# P02_MCU.net
KiCad netlist of a schematic drawn in Altium Designer
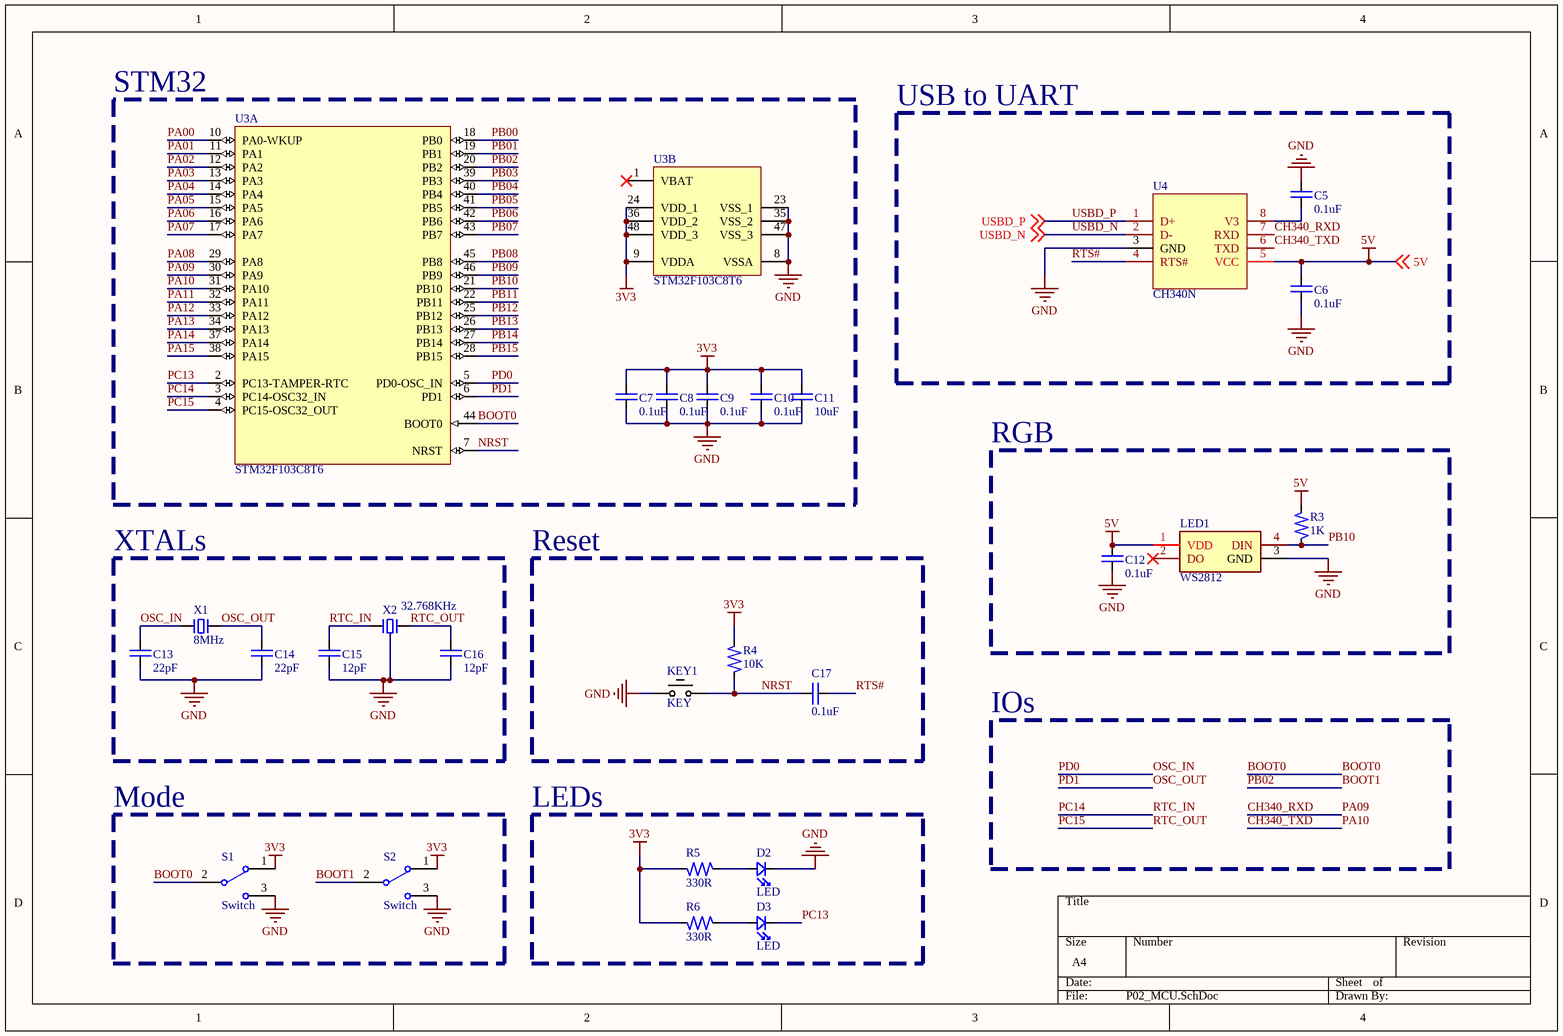
[diagram p0: P02_MCU.SchDoc]

(export (version "E")
  (design (tool "Eeschema 10.0.6"))
  (components
    (comp (ref "C5")
      (value "0.1uF")
      (footprint "C_0603")
      (description "无极性电容")
      (libsource (lib "Schlib") (part "C"))
    )
    (comp (ref "C6")
      (value "0.1uF")
      (footprint "C_0603")
      (description "无极性电容")
      (libsource (lib "Schlib") (part "C"))
    )
    (comp (ref "C7")
      (value "0.1uF")
      (footprint "C_0603")
      (description "无极性电容")
      (libsource (lib "Schlib") (part "C"))
    )
    (comp (ref "C8")
      (value "0.1uF")
      (footprint "C_0603")
      (description "无极性电容")
      (libsource (lib "Schlib") (part "C"))
    )
    (comp (ref "C9")
      (value "0.1uF")
      (footprint "C_0603")
      (description "无极性电容")
      (libsource (lib "Schlib") (part "C"))
    )
    (comp (ref "C10")
      (value "0.1uF")
      (footprint "C_0603")
      (description "无极性电容")
      (libsource (lib "Schlib") (part "C"))
    )
    (comp (ref "C11")
      (value "10uF")
      (footprint "C_0603")
      (description "无极性电容")
      (libsource (lib "Schlib") (part "C"))
    )
    (comp (ref "C12")
      (value "0.1uF")
      (footprint "C_0603")
      (description "无极性电容")
      (libsource (lib "Schlib") (part "C"))
    )
    (comp (ref "C13")
      (value "22pF")
      (footprint "C_0603")
      (description "无极性电容")
      (libsource (lib "Schlib") (part "C"))
    )
    (comp (ref "C14")
      (value "22pF")
      (footprint "C_0603")
      (description "无极性电容")
      (libsource (lib "Schlib") (part "C"))
    )
    (comp (ref "C15")
      (value "12pF")
      (footprint "C_0603")
      (description "无极性电容")
      (libsource (lib "Schlib") (part "C"))
    )
    (comp (ref "C16")
      (value "12pF")
      (footprint "C_0603")
      (description "无极性电容")
      (libsource (lib "Schlib") (part "C"))
    )
    (comp (ref "C17")
      (value "0.1uF")
      (footprint "C_0603")
      (description "无极性电容")
      (libsource (lib "Schlib") (part "C"))
    )
    (comp (ref "D2")
      (value "LED")
      (footprint "LED_0603")
      (description "Diode")
      (libsource (lib "Schlib") (part "LED"))
    )
    (comp (ref "D3")
      (value "LED")
      (footprint "LED_0603")
      (description "Diode")
      (libsource (lib "Schlib") (part "LED"))
    )
    (comp (ref "KEY1")
      (value "KEY")
      (footprint "KEY")
      (description "通用2脚按键")
      (libsource (lib "Schlib") (part "KEY"))
    )
    (comp (ref "LED1") (value "WS2812") (footprint "SMD5050") (libsource (lib "Schlib") (part "WS2812")))
    (comp (ref "R3")
      (value "1K")
      (footprint "R_0603")
      (description "Resistor")
      (libsource (lib "Schlib") (part "R"))
    )
    (comp (ref "R4")
      (value "10K")
      (footprint "R_0603")
      (description "Resistor")
      (libsource (lib "Schlib") (part "R"))
    )
    (comp (ref "R5")
      (value "330R")
      (footprint "R_0603")
      (description "Resistor")
      (libsource (lib "Schlib") (part "R"))
    )
    (comp (ref "R6")
      (value "330R")
      (footprint "R_0603")
      (description "Resistor")
      (libsource (lib "Schlib") (part "R"))
    )
    (comp (ref "S1")
      (value "Switch")
      (footprint "Sliding Switch_3P")
      (libsource (lib "Schlib") (part "Switch"))
    )
    (comp (ref "S2")
      (value "Switch")
      (footprint "Sliding Switch_3P")
      (libsource (lib "Schlib") (part "Switch"))
    )
    (comp (ref "U3")
      (value "STM32F103C8T6")
      (footprint "QFP-48")
      (libsource (lib "Schlib") (part "STM32F103C8T6"))
    )
    (comp (ref "U4")
      (value "CH340N")
      (footprint "SOP-8")
      (description "USB转UART")
      (libsource (lib "Schlib") (part "CH340N"))
    )
    (comp (ref "X1")
      (value "8MHz")
      (footprint "XTAL_HC49S")
      (description "晶振")
      (libsource (lib "Schlib") (part "XTAL"))
    )
    (comp (ref "X2")
      (value "32.768KHz")
      (footprint "XTAL_DT26")
      (description "晶振")
      (libsource (lib "Schlib") (part "XTAL_RTC"))
    )
  )
  (nets
    (net (code "1") (name "/BOOT0") (class "Default")
      (node (ref "S1") (pin "2") (pinfunction "2_2") (pintype "passive"))
      (node (ref "U3") (pin "44") (pinfunction "BOOT0_44") (pintype "input"))
    )
    (net (code "2") (name "/BOOT1") (class "Default")
      (node (ref "S2") (pin "2") (pinfunction "2_2") (pintype "passive"))
      (node (ref "U3") (pin "20") (pinfunction "PB2_20") (pintype "bidirectional"))
    )
    (net (code "3") (name "/CH340_RXD") (class "Default")
      (node (ref "U3") (pin "30") (pinfunction "PA9_30") (pintype "bidirectional"))
      (node (ref "U4") (pin "7") (pinfunction "RXD_7") (pintype "passive"))
    )
    (net (code "4") (name "/CH340_TXD") (class "Default")
      (node (ref "U3") (pin "31") (pinfunction "PA10_31") (pintype "bidirectional"))
      (node (ref "U4") (pin "6") (pinfunction "TXD_6") (pintype "passive"))
    )
    (net (code "5") (name "/NRST") (class "Default")
      (node (ref "C17") (pin "1") (pinfunction "1_1") (pintype "passive"))
      (node (ref "KEY1") (pin "1") (pinfunction "1_1") (pintype "passive"))
      (node (ref "R4") (pin "2") (pinfunction "2_2") (pintype "passive"))
      (node (ref "U3") (pin "7") (pinfunction "NRST_7") (pintype "bidirectional"))
    )
    (net (code "6") (name "/OSC_IN") (class "Default")
      (node (ref "C13") (pin "1") (pinfunction "1_1") (pintype "passive"))
      (node (ref "U3") (pin "5") (pinfunction "PD0-OSC_IN_5") (pintype "bidirectional"))
      (node (ref "X1") (pin "1") (pinfunction "1_1") (pintype "passive"))
    )
    (net (code "7") (name "/OSC_OUT") (class "Default")
      (node (ref "C14") (pin "1") (pinfunction "1_1") (pintype "passive"))
      (node (ref "U3") (pin "6") (pinfunction "PD1_6") (pintype "bidirectional"))
      (node (ref "X1") (pin "2") (pinfunction "2_2") (pintype "passive"))
    )
    (net (code "8") (name "/PA00") (class "Default")
      (node (ref "U3") (pin "10") (pinfunction "PA0-WKUP_10") (pintype "bidirectional"))
    )
    (net (code "9") (name "/PA01") (class "Default")
      (node (ref "U3") (pin "11") (pinfunction "PA1_11") (pintype "bidirectional"))
    )
    (net (code "10") (name "/PA02") (class "Default")
      (node (ref "U3") (pin "12") (pinfunction "PA2_12") (pintype "bidirectional"))
    )
    (net (code "11") (name "/PA03") (class "Default")
      (node (ref "U3") (pin "13") (pinfunction "PA3_13") (pintype "bidirectional"))
    )
    (net (code "12") (name "/PA04") (class "Default")
      (node (ref "U3") (pin "14") (pinfunction "PA4_14") (pintype "bidirectional"))
    )
    (net (code "13") (name "/PA05") (class "Default")
      (node (ref "U3") (pin "15") (pinfunction "PA5_15") (pintype "bidirectional"))
    )
    (net (code "14") (name "/PA06") (class "Default")
      (node (ref "U3") (pin "16") (pinfunction "PA6_16") (pintype "bidirectional"))
    )
    (net (code "15") (name "/PA07") (class "Default")
      (node (ref "U3") (pin "17") (pinfunction "PA7_17") (pintype "bidirectional"))
    )
    (net (code "16") (name "/PA08") (class "Default")
      (node (ref "U3") (pin "29") (pinfunction "PA8_29") (pintype "bidirectional"))
    )
    (net (code "17") (name "/PA11") (class "Default")
      (node (ref "U3") (pin "32") (pinfunction "PA11_32") (pintype "bidirectional"))
    )
    (net (code "18") (name "/PA12") (class "Default")
      (node (ref "U3") (pin "33") (pinfunction "PA12_33") (pintype "bidirectional"))
    )
    (net (code "19") (name "/PA13") (class "Default")
      (node (ref "U3") (pin "34") (pinfunction "PA13_34") (pintype "bidirectional"))
    )
    (net (code "20") (name "/PA14") (class "Default")
      (node (ref "U3") (pin "37") (pinfunction "PA14_37") (pintype "bidirectional"))
    )
    (net (code "21") (name "/PA15") (class "Default")
      (node (ref "U3") (pin "38") (pinfunction "PA15_38") (pintype "bidirectional"))
    )
    (net (code "22") (name "/PB00") (class "Default")
      (node (ref "U3") (pin "18") (pinfunction "PB0_18") (pintype "bidirectional"))
    )
    (net (code "23") (name "/PB01") (class "Default")
      (node (ref "U3") (pin "19") (pinfunction "PB1_19") (pintype "bidirectional"))
    )
    (net (code "24") (name "/PB03") (class "Default")
      (node (ref "U3") (pin "39") (pinfunction "PB3_39") (pintype "bidirectional"))
    )
    (net (code "25") (name "/PB04") (class "Default")
      (node (ref "U3") (pin "40") (pinfunction "PB4_40") (pintype "bidirectional"))
    )
    (net (code "26") (name "/PB05") (class "Default")
      (node (ref "U3") (pin "41") (pinfunction "PB5_41") (pintype "bidirectional"))
    )
    (net (code "27") (name "/PB06") (class "Default")
      (node (ref "U3") (pin "42") (pinfunction "PB6_42") (pintype "bidirectional"))
    )
    (net (code "28") (name "/PB07") (class "Default")
      (node (ref "U3") (pin "43") (pinfunction "PB7_43") (pintype "bidirectional"))
    )
    (net (code "29") (name "/PB08") (class "Default")
      (node (ref "U3") (pin "45") (pinfunction "PB8_45") (pintype "bidirectional"))
    )
    (net (code "30") (name "/PB09") (class "Default")
      (node (ref "U3") (pin "46") (pinfunction "PB9_46") (pintype "bidirectional"))
    )
    (net (code "31") (name "/PB10") (class "Default")
      (node (ref "LED1") (pin "4") (pinfunction "DIN_4") (pintype "passive"))
      (node (ref "R3") (pin "1") (pinfunction "1_1") (pintype "passive"))
      (node (ref "U3") (pin "21") (pinfunction "PB10_21") (pintype "bidirectional"))
    )
    (net (code "32") (name "/PB11") (class "Default")
      (node (ref "U3") (pin "22") (pinfunction "PB11_22") (pintype "bidirectional"))
    )
    (net (code "33") (name "/PB12") (class "Default")
      (node (ref "U3") (pin "25") (pinfunction "PB12_25") (pintype "bidirectional"))
    )
    (net (code "34") (name "/PB13") (class "Default")
      (node (ref "U3") (pin "26") (pinfunction "PB13_26") (pintype "bidirectional"))
    )
    (net (code "35") (name "/PB14") (class "Default")
      (node (ref "U3") (pin "27") (pinfunction "PB14_27") (pintype "bidirectional"))
    )
    (net (code "36") (name "/PB15") (class "Default")
      (node (ref "U3") (pin "28") (pinfunction "PB15_28") (pintype "bidirectional"))
    )
    (net (code "37") (name "/PC13") (class "Default")
      (node (ref "D3") (pin "1") (pinfunction "1_1") (pintype "passive"))
      (node (ref "U3") (pin "2") (pinfunction "PC13-TAMPER-RTC_2") (pintype "bidirectional"))
    )
    (net (code "38") (name "/PC14") (class "Default")
      (node (ref "C15") (pin "1") (pinfunction "1_1") (pintype "passive"))
      (node (ref "U3") (pin "3") (pinfunction "PC14-OSC32_IN_3") (pintype "bidirectional"))
      (node (ref "X2") (pin "1") (pinfunction "1_1") (pintype "passive"))
    )
    (net (code "39") (name "/PC15") (class "Default")
      (node (ref "C16") (pin "1") (pinfunction "1_1") (pintype "passive"))
      (node (ref "U3") (pin "4") (pinfunction "PC15-OSC32_OUT_4") (pintype "bidirectional"))
      (node (ref "X2") (pin "2") (pinfunction "2_2") (pintype "passive"))
    )
    (net (code "40") (name "/RTS#") (class "Default")
      (node (ref "C17") (pin "2") (pinfunction "2_2") (pintype "passive"))
      (node (ref "U4") (pin "4") (pinfunction "RTS#_4") (pintype "passive"))
    )
    (net (code "41") (name "3V3") (class "Default")
      (node (ref "C10") (pin "2") (pinfunction "2_2") (pintype "passive"))
      (node (ref "C11") (pin "2") (pinfunction "2_2") (pintype "passive"))
      (node (ref "C7") (pin "1") (pinfunction "1_1") (pintype "passive"))
      (node (ref "C8") (pin "2") (pinfunction "2_2") (pintype "passive"))
      (node (ref "C9") (pin "2") (pinfunction "2_2") (pintype "passive"))
      (node (ref "R4") (pin "1") (pinfunction "1_1") (pintype "passive"))
      (node (ref "R5") (pin "1") (pinfunction "1_1") (pintype "passive"))
      (node (ref "R6") (pin "1") (pinfunction "1_1") (pintype "passive"))
      (node (ref "S1") (pin "1") (pinfunction "1_1") (pintype "passive"))
      (node (ref "S2") (pin "1") (pinfunction "1_1") (pintype "passive"))
      (node (ref "U3") (pin "24") (pinfunction "VDD_1_24") (pintype "power_in"))
      (node (ref "U3") (pin "36") (pinfunction "VDD_2_36") (pintype "power_in"))
      (node (ref "U3") (pin "48") (pinfunction "VDD_3_48") (pintype "power_in"))
      (node (ref "U3") (pin "9") (pinfunction "VDDA_9") (pintype "power_in"))
    )
    (net (code "42") (name "5V") (class "Default")
      (node (ref "C12") (pin "1") (pinfunction "1_1") (pintype "passive"))
      (node (ref "C6") (pin "1") (pinfunction "1_1") (pintype "passive"))
      (node (ref "LED1") (pin "1") (pinfunction "VDD_1") (pintype "passive"))
      (node (ref "R3") (pin "2") (pinfunction "2_2") (pintype "passive"))
      (node (ref "U4") (pin "5") (pinfunction "VCC_5") (pintype "passive"))
    )
    (net (code "43") (name "GND") (class "Default")
      (node (ref "C10") (pin "1") (pinfunction "1_1") (pintype "passive"))
      (node (ref "C11") (pin "1") (pinfunction "1_1") (pintype "passive"))
      (node (ref "C12") (pin "2") (pinfunction "2_2") (pintype "passive"))
      (node (ref "C13") (pin "2") (pinfunction "2_2") (pintype "passive"))
      (node (ref "C14") (pin "2") (pinfunction "2_2") (pintype "passive"))
      (node (ref "C15") (pin "2") (pinfunction "2_2") (pintype "passive"))
      (node (ref "C16") (pin "2") (pinfunction "2_2") (pintype "passive"))
      (node (ref "C5") (pin "1") (pinfunction "1_1") (pintype "passive"))
      (node (ref "C6") (pin "2") (pinfunction "2_2") (pintype "passive"))
      (node (ref "C7") (pin "2") (pinfunction "2_2") (pintype "passive"))
      (node (ref "C8") (pin "1") (pinfunction "1_1") (pintype "passive"))
      (node (ref "C9") (pin "1") (pinfunction "1_1") (pintype "passive"))
      (node (ref "D2") (pin "1") (pinfunction "1_1") (pintype "passive"))
      (node (ref "KEY1") (pin "2") (pinfunction "2_2") (pintype "passive"))
      (node (ref "LED1") (pin "3") (pinfunction "GND_3") (pintype "passive"))
      (node (ref "S1") (pin "3") (pinfunction "3_3") (pintype "passive"))
      (node (ref "S2") (pin "3") (pinfunction "3_3") (pintype "passive"))
      (node (ref "U3") (pin "23") (pinfunction "VSS_1_23") (pintype "power_in"))
      (node (ref "U3") (pin "35") (pinfunction "VSS_2_35") (pintype "power_in"))
      (node (ref "U3") (pin "47") (pinfunction "VSS_3_47") (pintype "power_in"))
      (node (ref "U3") (pin "8") (pinfunction "VSSA_8") (pintype "power_in"))
      (node (ref "U4") (pin "3") (pinfunction "GND_3") (pintype "passive"))
      (node (ref "X2") (pin "0") (pinfunction "0_0") (pintype "passive"))
    )
    (net (code "44") (name "Net-(D2-Pad2)") (class "Default")
      (node (ref "D2") (pin "2") (pinfunction "2_2") (pintype "passive"))
      (node (ref "R5") (pin "2") (pinfunction "2_2") (pintype "passive"))
    )
    (net (code "45") (name "Net-(D3-Pad2)") (class "Default")
      (node (ref "D3") (pin "2") (pinfunction "2_2") (pintype "passive"))
      (node (ref "R6") (pin "2") (pinfunction "2_2") (pintype "passive"))
    )
    (net (code "46") (name "Net-(U4-V3)") (class "Default")
      (node (ref "C5") (pin "2") (pinfunction "2_2") (pintype "passive"))
      (node (ref "U4") (pin "8") (pinfunction "V3_8") (pintype "passive"))
    )
    (net (code "47") (name "USBD_N") (class "Default")
      (node (ref "U4") (pin "2") (pinfunction "D-_2") (pintype "passive"))
    )
    (net (code "48") (name "USBD_P") (class "Default")
      (node (ref "U4") (pin "1") (pinfunction "D+_1") (pintype "passive"))
    )
    (net (code "49") (name "unconnected-(LED1-DO-Pad2)") (class "Default")
      (node (ref "LED1") (pin "2") (pinfunction "DO_2") (pintype "passive+no_connect"))
    )
    (net (code "50") (name "unconnected-(U3B-VBAT-Pad1)") (class "Default")
      (node (ref "U3") (pin "1") (pinfunction "VBAT_1") (pintype "power_in+no_connect"))
    )
  )
)
